# AnalogBoard.net
KiCad netlist of a schematic drawn in EAGLE
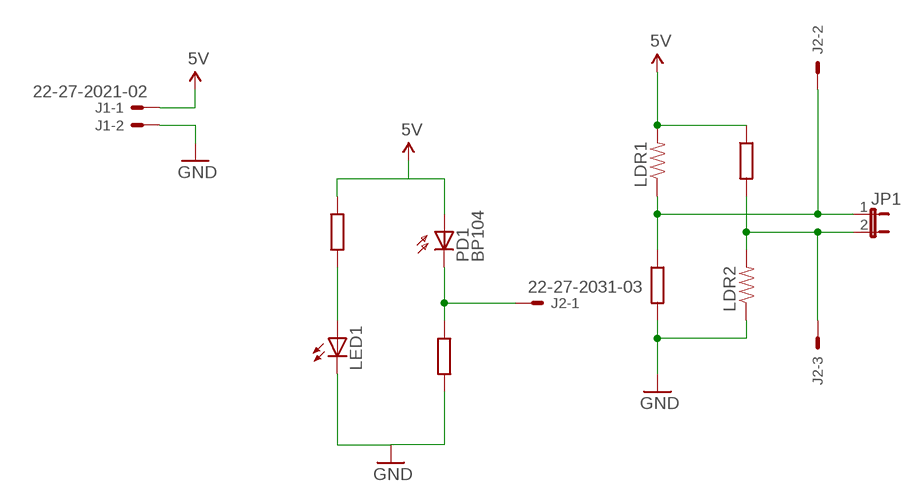
[diagram p0: schematic, sheet 1]

(export (version "E")
  (design (tool "Eeschema 10.0.6"))
  (components
    (comp (ref "J1")
      (value "22-27-2021-02")
      (footprint "eagle-import:6410-02")
      (libsource (lib "eagle-import") (part "22-?-0227-2021"))
    )
    (comp (ref "J2")
      (value "22-27-2031-03")
      (footprint "eagle-import:6410-03")
      (libsource (lib "eagle-import") (part "22-?-0327-2031"))
    )
    (comp (ref "JP1")
      (value "JP1E")
      (footprint "eagle-import:JP1")
      (libsource (lib "eagle-import") (part "JP1E"))
    )
    (comp (ref "LDR1")
      (value "RESISTORPTH-1/4W")
      (footprint "eagle-import:AXIAL-0.4")
      (libsource (lib "eagle-import") (part "RESISTORPTH-1/4W"))
    )
    (comp (ref "LDR2")
      (value "RESISTORPTH-1/4W")
      (footprint "eagle-import:AXIAL-0.4")
      (libsource (lib "eagle-import") (part "RESISTORPTH-1/4W"))
    )
    (comp (ref "LED1")
      (value "LED3MM")
      (footprint "eagle-import:LED3MM")
      (libsource (lib "eagle-import") (part "LED3MM"))
    )
    (comp (ref "PD1")
      (value "BP104")
      (footprint "eagle-import:BP104")
      (fields (field (name "MF") "VISHAY/TELEFUNKEN"))
      (libsource (lib "eagle-import") (part "BP104"))
    )
  )
  (nets
    (net (code "1") (name "5V") (class "Default")
      (node (ref "J1") (pin "1") (pinfunction "S_1") (pintype "passive"))
      (node (ref "LDR1") (pin "P$2") (pinfunction "2_P$2") (pintype "passive"))
      (node (ref "PD1") (pin "A") (pinfunction "A_A") (pintype "passive"))
    )
    (net (code "2") (name "GND") (class "Default")
      (node (ref "J1") (pin "2") (pinfunction "S_2") (pintype "passive"))
      (node (ref "LDR2") (pin "P$1") (pinfunction "1_P$1") (pintype "passive"))
      (node (ref "LED1") (pin "K") (pinfunction "C_K") (pintype "passive"))
    )
    (net (code "3") (name "Net-(J2A-S)") (class "Default")
      (node (ref "J2") (pin "1") (pinfunction "S_1") (pintype "passive"))
      (node (ref "PD1") (pin "K") (pinfunction "C_K") (pintype "passive"))
    )
    (net (code "4") (name "Net-(J2B-S)") (class "Default")
      (node (ref "J2") (pin "2") (pinfunction "S_2") (pintype "passive"))
      (node (ref "JP1") (pin "1") (pinfunction "1_1") (pintype "passive"))
      (node (ref "LDR1") (pin "P$1") (pinfunction "1_P$1") (pintype "passive"))
    )
    (net (code "5") (name "Net-(J2C-S)") (class "Default")
      (node (ref "J2") (pin "3") (pinfunction "S_3") (pintype "passive"))
      (node (ref "JP1") (pin "2") (pinfunction "2_2") (pintype "passive"))
      (node (ref "LDR2") (pin "P$2") (pinfunction "2_P$2") (pintype "passive"))
    )
    (net (code "6") (name "unconnected-(LED1-PadA)") (class "Default")
      (node (ref "LED1") (pin "A") (pinfunction "A_A") (pintype "passive"))
    )
  )
)
